# connector_cooler.net
KiCad netlist of a schematic drawn in Altium Designer
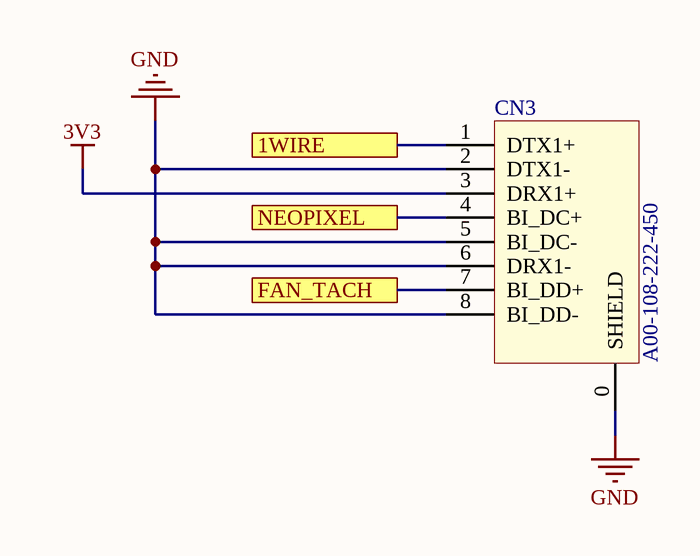
[diagram p0: connector_cooler.SchDoc]

(export (version "E")
  (design (tool "Eeschema 10.0.6"))
  (components
    (comp (ref "CN3")
      (value "CONN_RJ45_TOP_A00-108-222-450")
      (footprint "RJ45 TOP ENTRY EDAC A00-108-222-450")
      (description "CONN, RJ-45, 1-PORT, 8-POS, VERT, 0.76um GOLD, TH")
      (fields (field (name "MFG") "EDAC Inc") (field (name "MFG P/N") "A00-108-222-450"))
      (libsource (lib "AltiumReleaseLibDB") (part "CONN_RJ45_TOP_A00-108-222-450"))
    )
  )
  (nets
    (net (code "1") (name "/1WIRE") (class "Default")
      (node (ref "CN3") (pin "1") (pinfunction "DTX1+_1") (pintype "passive"))
    )
    (net (code "2") (name "/FAN_TACH") (class "Default")
      (node (ref "CN3") (pin "7") (pinfunction "BI_DD+_7") (pintype "passive"))
    )
    (net (code "3") (name "/NEOPIXEL") (class "Default")
      (node (ref "CN3") (pin "4") (pinfunction "BI_DC+_4") (pintype "passive"))
    )
    (net (code "4") (name "3V3") (class "Default")
      (node (ref "CN3") (pin "3") (pinfunction "DRX1+_3") (pintype "passive"))
    )
    (net (code "5") (name "GND") (class "Default")
      (node (ref "CN3") (pin "0") (pinfunction "SHIELD_0") (pintype "passive"))
      (node (ref "CN3") (pin "2") (pinfunction "DTX1-_2") (pintype "passive"))
      (node (ref "CN3") (pin "5") (pinfunction "BI_DC-_5") (pintype "passive"))
      (node (ref "CN3") (pin "6") (pinfunction "DRX1-_6") (pintype "passive"))
      (node (ref "CN3") (pin "8") (pinfunction "BI_DD-_8") (pintype "passive"))
    )
  )
)
